# ds3231_breakout.net
KiCad netlist of a schematic drawn in EAGLE
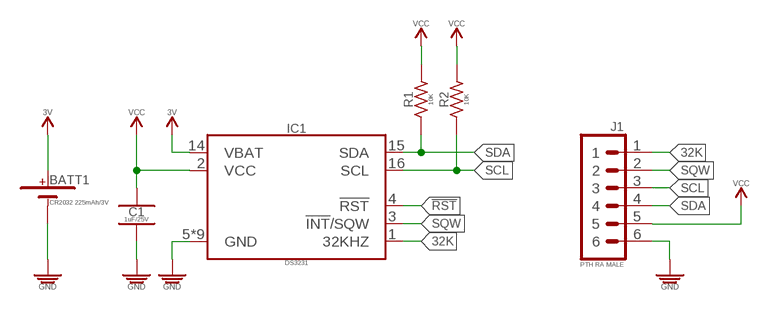
[diagram p0: schematic, sheet 1]

(export (version "E")
  (design (tool "Eeschema 10.0.6"))
  (components
    (comp (ref "BATT1")
      (value "CR2032 225mAh/3V")
      (footprint "eagle-import:BATTERY_COINCELL-20MM-PTH")
      (fields (field (name "MFR") "Panasonic - BSG") (field (name "MPN") "CR2032"))
      (libsource (lib "eagle-import") (part "BATTERY_COIN-CELL_PTH_3V_20MM"))
    )
    (comp (ref "C1")
      (value "1uF/25V")
      (footprint "eagle-import:CAPC1005X55_SMD-0402")
      (fields (field (name "MFR") "TDK Corporation") (field (name "MPN") "CGB2A1X5R1E105K033BC"))
      (libsource (lib "eagle-import") (part "1UF_CER_SMD-0402_25V-10%"))
    )
    (comp (ref "IC1")
      (value "DS3231")
      (footprint "eagle-import:SOIC127P1032X265-16")
      (fields (field (name "MFR") "Maxim Integrated") (field (name "MPN") "DS3231S#T&R"))
      (libsource (lib "eagle-import") (part "DS3231_DS3231_RTC_CLK_I2C_SOIC-16"))
    )
    (comp (ref "J1")
      (value "PTH RA MALE")
      (footprint "eagle-import:HDRRA6W64P254_1X6_1524X254X254B")
      (fields (field (name "MFR") "Sullins Connector Solutions") (field (name "MPN") "PEC06SBAN"))
      (libsource (lib "eagle-import") (part "1X06PTH_RA_MALE_2.54MM"))
    )
    (comp (ref "R1")
      (value "10K")
      (footprint "eagle-import:RESC1005X35_SMD-0402")
      (fields (field (name "MFR") "Yageo") (field (name "MPN") "RC0402JR-0710KP"))
      (libsource (lib "eagle-import") (part "10KΩ_SMD-0402_1/16W-5%"))
    )
    (comp (ref "R2")
      (value "10K")
      (footprint "eagle-import:RESC1005X35_SMD-0402")
      (fields (field (name "MFR") "Yageo") (field (name "MPN") "RC0402JR-0710KP"))
      (libsource (lib "eagle-import") (part "10KΩ_SMD-0402_1/16W-5%"))
    )
  )
  (nets
    (net (code "1") (name "/~{RST}") (class "Default")
      (node (ref "IC1") (pin "4") (pinfunction "~{RST}_4") (pintype "bidirectional"))
    )
    (net (code "2") (name "3V") (class "Default")
      (node (ref "BATT1") (pin "+") (pinfunction "+_+") (pintype "passive"))
      (node (ref "IC1") (pin "14") (pinfunction "VBAT_14") (pintype "bidirectional"))
    )
    (net (code "3") (name "32K") (class "Default")
      (node (ref "IC1") (pin "1") (pinfunction "32KHZ_1") (pintype "bidirectional"))
      (node (ref "J1") (pin "1") (pinfunction "1_1") (pintype "passive"))
    )
    (net (code "4") (name "GND") (class "Default")
      (node (ref "BATT1") (pin "-") (pinfunction "-_-") (pintype "passive"))
      (node (ref "C1") (pin "2") (pinfunction "2_2") (pintype "passive"))
      (node (ref "IC1") (pin "10") (pinfunction "GND_10") (pintype "bidirectional"))
      (node (ref "IC1") (pin "11") (pinfunction "GND_11") (pintype "bidirectional"))
      (node (ref "IC1") (pin "12") (pinfunction "GND_12") (pintype "bidirectional"))
      (node (ref "IC1") (pin "13") (pinfunction "GND_13") (pintype "bidirectional"))
      (node (ref "IC1") (pin "5") (pinfunction "GND_5") (pintype "bidirectional"))
      (node (ref "IC1") (pin "6") (pinfunction "GND_6") (pintype "bidirectional"))
      (node (ref "IC1") (pin "7") (pinfunction "GND_7") (pintype "bidirectional"))
      (node (ref "IC1") (pin "8") (pinfunction "GND_8") (pintype "bidirectional"))
      (node (ref "IC1") (pin "9") (pinfunction "GND_9") (pintype "bidirectional"))
      (node (ref "J1") (pin "6") (pinfunction "6_6") (pintype "passive"))
    )
    (net (code "5") (name "SCL") (class "Default")
      (node (ref "IC1") (pin "16") (pinfunction "SCL_16") (pintype "bidirectional"))
      (node (ref "J1") (pin "3") (pinfunction "3_3") (pintype "passive"))
      (node (ref "R2") (pin "1") (pinfunction "1_1") (pintype "passive"))
    )
    (net (code "6") (name "SDA") (class "Default")
      (node (ref "IC1") (pin "15") (pinfunction "SDA_15") (pintype "bidirectional"))
      (node (ref "J1") (pin "4") (pinfunction "4_4") (pintype "passive"))
      (node (ref "R1") (pin "1") (pinfunction "1_1") (pintype "passive"))
    )
    (net (code "7") (name "SQW") (class "Default")
      (node (ref "IC1") (pin "3") (pinfunction "~{INT}/SQW_3") (pintype "bidirectional"))
      (node (ref "J1") (pin "2") (pinfunction "2_2") (pintype "passive"))
    )
    (net (code "8") (name "VCC") (class "Default")
      (node (ref "C1") (pin "1") (pinfunction "1_1") (pintype "passive"))
      (node (ref "IC1") (pin "2") (pinfunction "VCC_2") (pintype "bidirectional"))
      (node (ref "J1") (pin "5") (pinfunction "5_5") (pintype "passive"))
      (node (ref "R1") (pin "2") (pinfunction "2_2") (pintype "passive"))
      (node (ref "R2") (pin "2") (pinfunction "2_2") (pintype "passive"))
    )
  )
)
